# lamps-manual.net
KiCad netlist of a schematic drawn in EAGLE
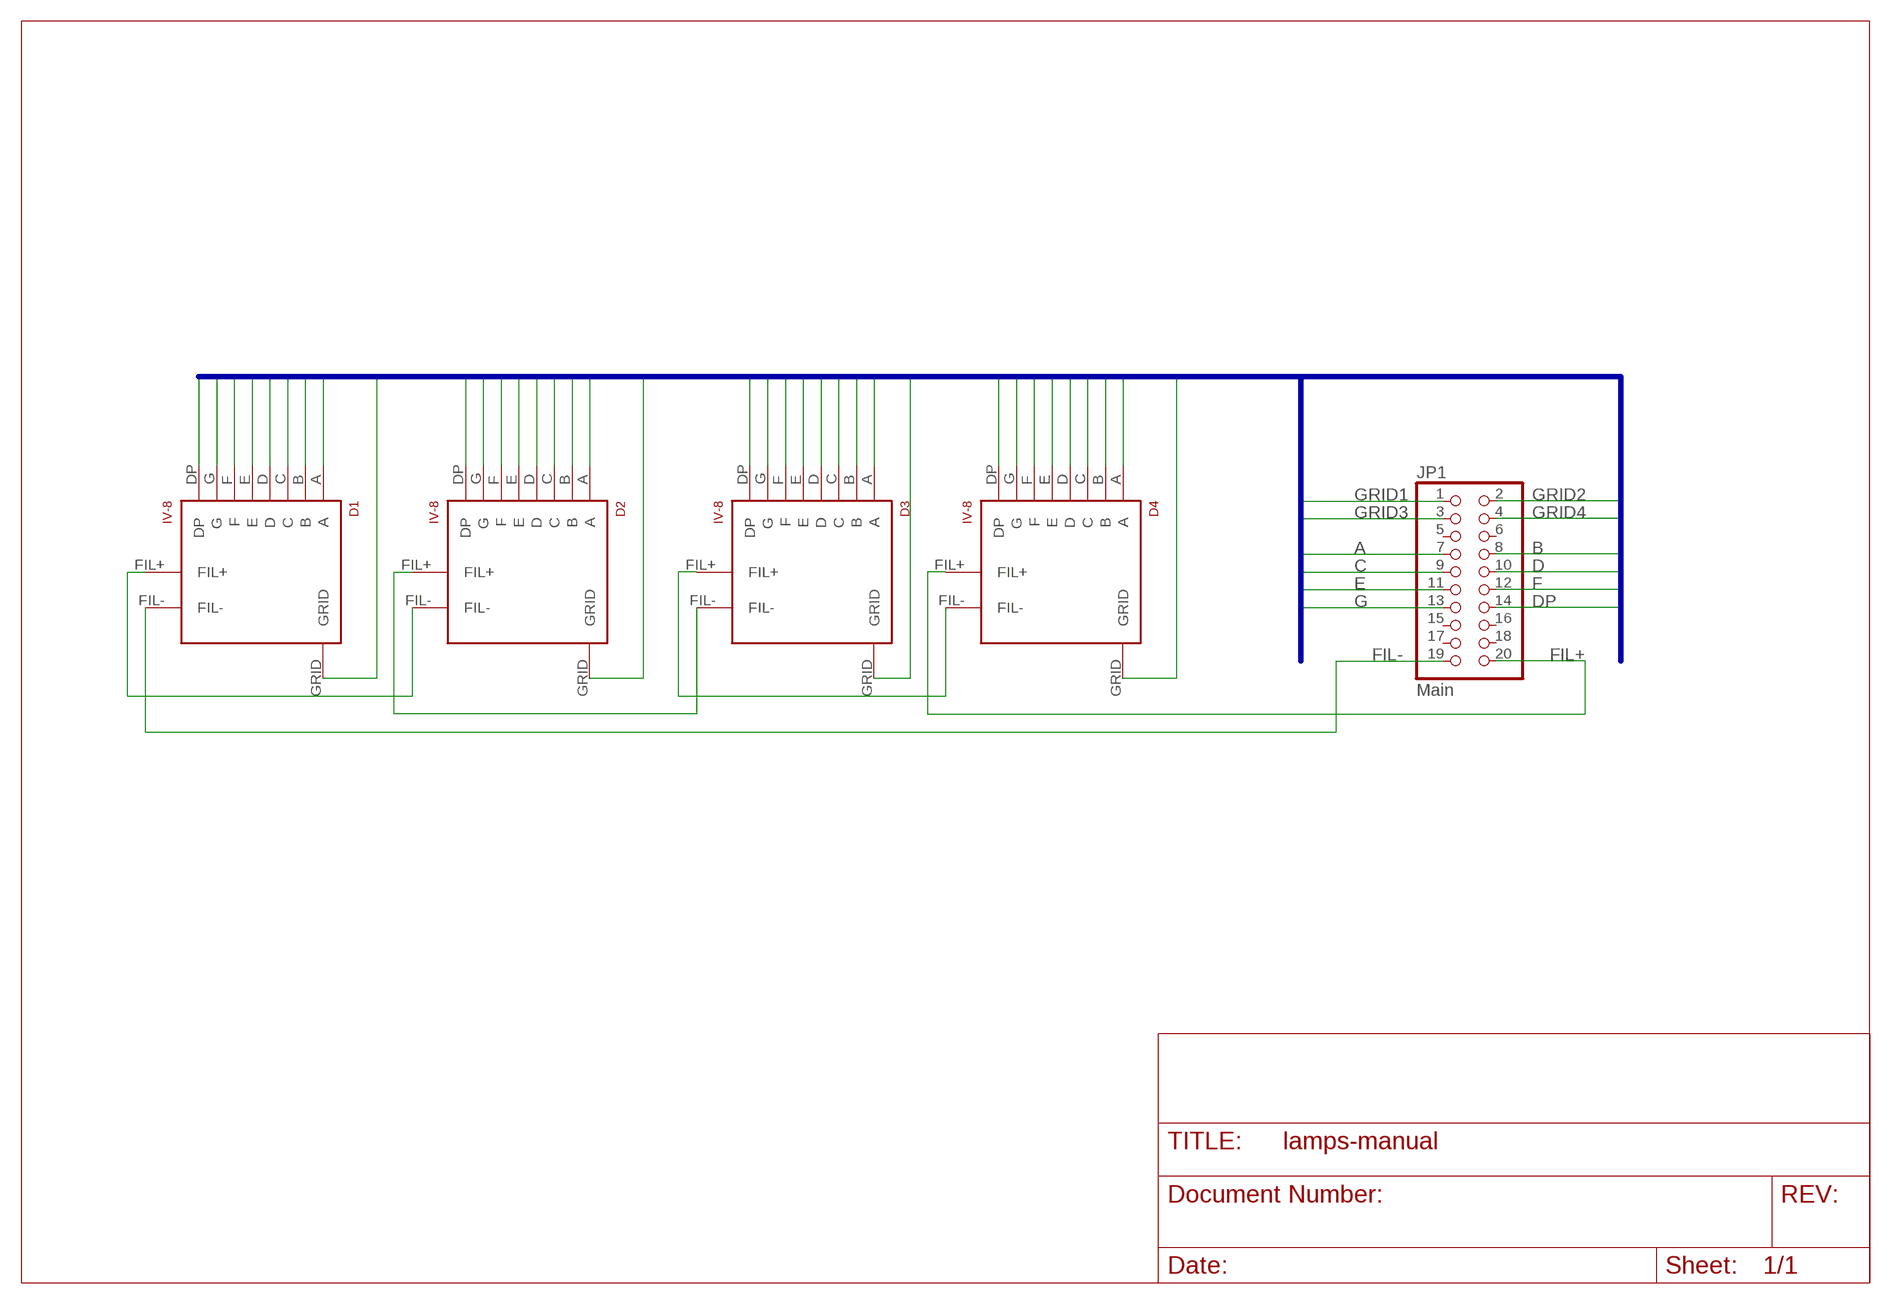
[diagram p0: schematic, sheet 1]

(export (version "E")
  (design (tool "Eeschema 10.0.6"))
  (components
    (comp (ref "D1")
      (value "IV-8")
      (footprint "eagle-import:IV-8")
      (libsource (lib "eagle-import") (part "IV-8"))
    )
    (comp (ref "D2")
      (value "IV-8")
      (footprint "eagle-import:IV-8")
      (libsource (lib "eagle-import") (part "IV-8"))
    )
    (comp (ref "D3")
      (value "IV-8")
      (footprint "eagle-import:IV-8")
      (libsource (lib "eagle-import") (part "IV-8"))
    )
    (comp (ref "D4")
      (value "IV-8")
      (footprint "eagle-import:IV-8")
      (libsource (lib "eagle-import") (part "IV-8"))
    )
    (comp (ref "JP1")
      (value "Main")
      (footprint "eagle-import:2X10")
      (libsource (lib "eagle-import") (part "PINHD-2X10"))
    )
  )
  (nets
    (net (code "1") (name "/A") (class "Default")
      (node (ref "D1") (pin "A") (pinfunction "A_A") (pintype "input"))
      (node (ref "D2") (pin "A") (pinfunction "A_A") (pintype "input"))
      (node (ref "D3") (pin "A") (pinfunction "A_A") (pintype "input"))
      (node (ref "D4") (pin "A") (pinfunction "A_A") (pintype "input"))
      (node (ref "JP1") (pin "7") (pinfunction "A_7") (pintype "passive"))
    )
    (net (code "2") (name "/B") (class "Default")
      (node (ref "D1") (pin "B") (pinfunction "B_B") (pintype "input"))
      (node (ref "D2") (pin "B") (pinfunction "B_B") (pintype "input"))
      (node (ref "D3") (pin "B") (pinfunction "B_B") (pintype "input"))
      (node (ref "D4") (pin "B") (pinfunction "B_B") (pintype "input"))
      (node (ref "JP1") (pin "8") (pinfunction "B_8") (pintype "passive"))
    )
    (net (code "3") (name "/C") (class "Default")
      (node (ref "D1") (pin "C") (pinfunction "C_C") (pintype "bidirectional"))
      (node (ref "D2") (pin "C") (pinfunction "C_C") (pintype "bidirectional"))
      (node (ref "D3") (pin "C") (pinfunction "C_C") (pintype "bidirectional"))
      (node (ref "D4") (pin "C") (pinfunction "C_C") (pintype "bidirectional"))
      (node (ref "JP1") (pin "9") (pinfunction "C_9") (pintype "passive"))
    )
    (net (code "4") (name "/D") (class "Default")
      (node (ref "D1") (pin "D") (pinfunction "D_D") (pintype "input"))
      (node (ref "D2") (pin "D") (pinfunction "D_D") (pintype "input"))
      (node (ref "D3") (pin "D") (pinfunction "D_D") (pintype "input"))
      (node (ref "D4") (pin "D") (pinfunction "D_D") (pintype "input"))
      (node (ref "JP1") (pin "10") (pinfunction "D_10") (pintype "passive"))
    )
    (net (code "5") (name "/DP") (class "Default")
      (node (ref "D1") (pin "DP") (pinfunction "DP_DP") (pintype "bidirectional"))
      (node (ref "D2") (pin "DP") (pinfunction "DP_DP") (pintype "bidirectional"))
      (node (ref "D3") (pin "DP") (pinfunction "DP_DP") (pintype "bidirectional"))
      (node (ref "D4") (pin "DP") (pinfunction "DP_DP") (pintype "bidirectional"))
      (node (ref "JP1") (pin "14") (pinfunction "DP_14") (pintype "passive"))
    )
    (net (code "6") (name "/E") (class "Default")
      (node (ref "D1") (pin "E") (pinfunction "E_E") (pintype "bidirectional"))
      (node (ref "D2") (pin "E") (pinfunction "E_E") (pintype "bidirectional"))
      (node (ref "D3") (pin "E") (pinfunction "E_E") (pintype "bidirectional"))
      (node (ref "D4") (pin "E") (pinfunction "E_E") (pintype "bidirectional"))
      (node (ref "JP1") (pin "11") (pinfunction "E_11") (pintype "passive"))
    )
    (net (code "7") (name "/F") (class "Default")
      (node (ref "D1") (pin "F") (pinfunction "F_F") (pintype "bidirectional"))
      (node (ref "D2") (pin "F") (pinfunction "F_F") (pintype "bidirectional"))
      (node (ref "D3") (pin "F") (pinfunction "F_F") (pintype "bidirectional"))
      (node (ref "D4") (pin "F") (pinfunction "F_F") (pintype "bidirectional"))
      (node (ref "JP1") (pin "12") (pinfunction "F_12") (pintype "passive"))
    )
    (net (code "8") (name "/FIL+") (class "Default")
      (node (ref "D4") (pin "FIL+") (pinfunction "FIL+_FIL+") (pintype "bidirectional"))
      (node (ref "JP1") (pin "20") (pinfunction "FIL+_20") (pintype "passive"))
    )
    (net (code "9") (name "/FIL-") (class "Default")
      (node (ref "D1") (pin "FIL-") (pinfunction "FIL-_FIL-") (pintype "bidirectional"))
      (node (ref "JP1") (pin "19") (pinfunction "FIL-_19") (pintype "passive"))
    )
    (net (code "10") (name "/G") (class "Default")
      (node (ref "D1") (pin "G") (pinfunction "G_G") (pintype "bidirectional"))
      (node (ref "D2") (pin "G") (pinfunction "G_G") (pintype "bidirectional"))
      (node (ref "D3") (pin "G") (pinfunction "G_G") (pintype "bidirectional"))
      (node (ref "D4") (pin "G") (pinfunction "G_G") (pintype "bidirectional"))
      (node (ref "JP1") (pin "13") (pinfunction "G_13") (pintype "passive"))
    )
    (net (code "11") (name "/GRID1") (class "Default")
      (node (ref "D1") (pin "GRID") (pinfunction "GRID_GRID") (pintype "input"))
      (node (ref "JP1") (pin "1") (pinfunction "GRID1_1") (pintype "passive"))
    )
    (net (code "12") (name "/GRID2") (class "Default")
      (node (ref "D2") (pin "GRID") (pinfunction "GRID_GRID") (pintype "input"))
      (node (ref "JP1") (pin "2") (pinfunction "GRID2_2") (pintype "passive"))
    )
    (net (code "13") (name "/GRID3") (class "Default")
      (node (ref "D3") (pin "GRID") (pinfunction "GRID_GRID") (pintype "input"))
      (node (ref "JP1") (pin "3") (pinfunction "GRID3_3") (pintype "passive"))
    )
    (net (code "14") (name "/GRID4") (class "Default")
      (node (ref "D4") (pin "GRID") (pinfunction "GRID_GRID") (pintype "input"))
      (node (ref "JP1") (pin "4") (pinfunction "GRID4_4") (pintype "passive"))
    )
    (net (code "15") (name "Net-(D1-PadFIL+)") (class "Default")
      (node (ref "D1") (pin "FIL+") (pinfunction "FIL+_FIL+") (pintype "bidirectional"))
      (node (ref "D2") (pin "FIL-") (pinfunction "FIL-_FIL-") (pintype "bidirectional"))
    )
    (net (code "16") (name "Net-(D2-PadFIL+)") (class "Default")
      (node (ref "D2") (pin "FIL+") (pinfunction "FIL+_FIL+") (pintype "bidirectional"))
      (node (ref "D3") (pin "FIL-") (pinfunction "FIL-_FIL-") (pintype "bidirectional"))
    )
    (net (code "17") (name "Net-(D3-PadFIL+)") (class "Default")
      (node (ref "D3") (pin "FIL+") (pinfunction "FIL+_FIL+") (pintype "bidirectional"))
      (node (ref "D4") (pin "FIL-") (pinfunction "FIL-_FIL-") (pintype "bidirectional"))
    )
    (net (code "18") (name "unconnected-(JP1-GRID5-Pad5)") (class "Default")
      (node (ref "JP1") (pin "5") (pinfunction "GRID5_5") (pintype "passive"))
    )
    (net (code "19") (name "unconnected-(JP1-GRID6-Pad6)") (class "Default")
      (node (ref "JP1") (pin "6") (pinfunction "GRID6_6") (pintype "passive"))
    )
    (net (code "20") (name "unconnected-(JP1-Pad15)") (class "Default")
      (node (ref "JP1") (pin "15") (pinfunction "15_15") (pintype "passive"))
    )
    (net (code "21") (name "unconnected-(JP1-Pad16)") (class "Default")
      (node (ref "JP1") (pin "16") (pinfunction "16_16") (pintype "passive"))
    )
    (net (code "22") (name "unconnected-(JP1-Pad17)") (class "Default")
      (node (ref "JP1") (pin "17") (pinfunction "17_17") (pintype "passive"))
    )
    (net (code "23") (name "unconnected-(JP1-Pad18)") (class "Default")
      (node (ref "JP1") (pin "18") (pinfunction "18_18") (pintype "passive"))
    )
  )
)
